# Sheet1.net
KiCad netlist of a schematic drawn in Altium Designer
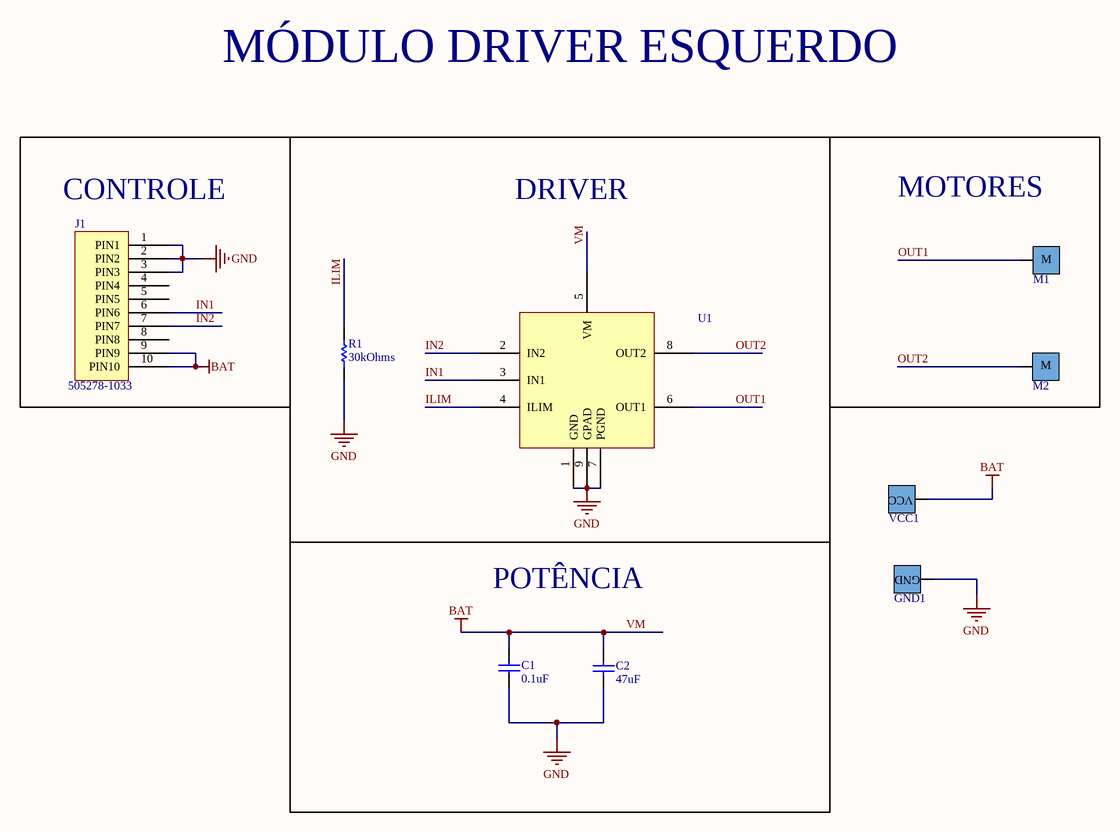
[diagram p0: Sheet1.SchDoc]

(export (version "E")
  (design (tool "Eeschema 10.0.6"))
  (components
    (comp (ref "C1")
      (value "0.1uF")
      (footprint "C0805")
      (description "CAP CER 100nF 25V X7R 0805")
      (fields
        (field (name "MANUFACTURER") "Kemet")
        (field (name "PART NUMBER") "C0805C104M3RACTU")
        (field (name "LIBRARY CONTROL - PERSON THAT CHECKED FOOTPRINT") "Cage")
        (field (name "LIBRARY CONTROL - PERSON THAT CHECKED SCHEMATIC") "Cage")
        (field (name "LIBRARY CONTROL - PERSON THAT DID THE LAST UPDATE FOOTPRINT") "Cage")
        (field (name "LIBRARY CONTROL - PERSON THAT DID THE LAST UPDATE SCHEMATIC") "Cage")
      )
      (libsource (lib "Uai!Tecas") (part "C0805C104M3RACTU"))
    )
    (comp (ref "C2")
      (value "47uF")
      (footprint "C1210")
      (description "CAP CER 47uF 16V X6S 1210")
      (fields
        (field (name "MANUFACTURER") "Murata")
        (field (name "PART NUMBER") "GRM32EC81C476KE15K")
        (field (name "LIBRARY CONTROL - PERSON THAT CHECKED FOOTPRINT") "Cage")
        (field (name "LIBRARY CONTROL - PERSON THAT CHECKED SCHEMATIC") "Cage")
        (field (name "LIBRARY CONTROL - PERSON THAT DID THE LAST UPDATE FOOTPRINT") "Prisma")
        (field (name "LIBRARY CONTROL - PERSON THAT DID THE LAST UPDATE SCHEMATIC") "Prisma")
      )
      (libsource (lib "Capacitor") (part "GRM32EC81C476KE15K"))
    )
    (comp (ref "GND1")
      (value "Ground Pad")
      (footprint "PAD_ALIMENTAÇÃO_MINI")
      (description "GND PAD MINI SUMÔ")
      (libsource (lib "Uai!Tecas") (part "Ground Pad Mini Sumô"))
    )
    (comp (ref "J1")
      (value "505278-1033")
      (footprint "FPC_CON")
      (description "CONN FFC/FPC HORZ 10POS 0.50MM")
      (fields
        (field (name "MANUFACTURER") "Molex")
        (field (name "LIBRARY CONTROL - PERSON THAT CHECKED FOOTPRINT") "Lucas")
        (field (name "LIBRARY CONTROL - PERSON THAT CHECKED SCHEMATIC") "Lucas")
        (field (name "LIBRARY CONTROL - PERSON THAT DID THE LAST UPDATE FOOTPRINT") "Mateus(Dimas)")
        (field (name "LIBRARY CONTROL - PERSON THAT DID THE LAST UPDATE SCHEMATIC") "Mateus(Dimas)")
      )
      (libsource (lib "Uai!Tecas") (part "505278-1033_BODY"))
    )
    (comp (ref "M1")
      (value "Motor Pad")
      (footprint "PAD_MOTOR_MINI")
      (description "MOTOR PAD MINI SUMÔ")
      (libsource (lib "Uai!Tecas") (part "Motor Pad Mini Sumô"))
    )
    (comp (ref "M2")
      (value "Motor Pad")
      (footprint "PAD_MOTOR_MINI")
      (description "MOTOR PAD MINI SUMÔ")
      (libsource (lib "Uai!Tecas") (part "Motor Pad Mini Sumô"))
    )
    (comp (ref "R1")
      (value "30kOhms")
      (footprint "RESC1608X55N")
      (description "RES SMD 30 kOHMS 1% 1/10W 0603")
      (fields
        (field (name "MANUFACTURER") "YAGEO")
        (field (name "PART NUMBER") "RC0603FR-0730KL")
        (field (name "LIBRARY CONTROL - PERSON THAT CHECKED FOOTPRINT") "Guilherme")
        (field (name "LIBRARY CONTROL - PERSON THAT CHECKED SCHEMATIC") "Guilherme")
        (field (name "LIBRARY CONTROL - PERSON THAT DID THE LAST UPDATE FOOTPRINT") "Guilherme")
        (field (name "LIBRARY CONTROL - PERSON THAT DID THE LAST UPDATE SCHEMATIC") "Guilherme")
      )
      (libsource (lib "Uai!Tecas") (part "RC0603FR-0730KL"))
    )
    (comp (ref "U1")
      (value "DRV8871DDA")
      (footprint "SO-PowerPad-8(8_pins)")
      (description "IC MTR DRV (6.5V ~ 45V) (3.5 A) SO-PowerPad-8")
      (fields
        (field (name "MANUFACTURER") "Texas Instruments")
        (field (name "LIBRARY CONTROL - PERSON THAT CHECKED SCHEMATIC") "Stéfany (Ster)")
        (field (name "LIBRARY CONTROL - PERSON THAT CHECKED FOOTPRINT") "Stéfany (Ster)")
        (field (name "LIBRARY CONTROL - PERSON THAT DID THE LAST UPDATE SCHEMATIC") "Stéfany (Ster)")
        (field (name "LIBRARY CONTROL - PERSON THAT DID THE LAST UPDATE FOOTPRINT") "Maria Laura")
      )
      (libsource (lib "Uai!Tecas") (part "DRV8871DDA"))
    )
    (comp (ref "VCC1")
      (value "Source Pad")
      (footprint "PAD_ALIMENTAÇÃO_MINI")
      (description "VCC PAD MINI SUMÔ")
      (libsource (lib "Uai!Tecas") (part "Source Pad Mini Sumô"))
    )
  )
  (nets
    (net (code "1") (name "/ILIM") (class "Default")
      (node (ref "R1") (pin "1") (pinfunction "1_1") (pintype "passive"))
      (node (ref "U1") (pin "4") (pinfunction "ILIM_4") (pintype "passive"))
    )
    (net (code "2") (name "/IN1") (class "Default")
      (node (ref "J1") (pin "6") (pinfunction "PIN6_6") (pintype "passive"))
      (node (ref "U1") (pin "3") (pinfunction "IN1_3") (pintype "passive"))
    )
    (net (code "3") (name "/IN2") (class "Default")
      (node (ref "J1") (pin "7") (pinfunction "PIN7_7") (pintype "passive"))
      (node (ref "U1") (pin "2") (pinfunction "IN2_2") (pintype "passive"))
    )
    (net (code "4") (name "/OUT1") (class "Default")
      (node (ref "M1") (pin "M") (pinfunction "M_M") (pintype "passive"))
      (node (ref "U1") (pin "6") (pinfunction "OUT1_6") (pintype "passive"))
    )
    (net (code "5") (name "/OUT2") (class "Default")
      (node (ref "M2") (pin "M") (pinfunction "M_M") (pintype "passive"))
      (node (ref "U1") (pin "8") (pinfunction "OUT2_8") (pintype "passive"))
    )
    (net (code "6") (name "BAT") (class "Default")
      (node (ref "C1") (pin "2") (pinfunction "2_2") (pintype "passive"))
      (node (ref "C2") (pin "2") (pinfunction "2_2") (pintype "passive"))
      (node (ref "J1") (pin "10") (pinfunction "PIN10_10") (pintype "passive"))
      (node (ref "J1") (pin "9") (pinfunction "PIN9_9") (pintype "passive"))
      (node (ref "U1") (pin "5") (pinfunction "VM_5") (pintype "passive"))
      (node (ref "VCC1") (pin "A") (pinfunction "VCC_A") (pintype "passive"))
    )
    (net (code "7") (name "GND") (class "Default")
      (node (ref "C1") (pin "1") (pinfunction "1_1") (pintype "passive"))
      (node (ref "C2") (pin "1") (pinfunction "1_1") (pintype "passive"))
      (node (ref "GND1") (pin "A") (pinfunction "GND_A") (pintype "passive"))
      (node (ref "J1") (pin "1") (pinfunction "PIN1_1") (pintype "passive"))
      (node (ref "J1") (pin "2") (pinfunction "PIN2_2") (pintype "passive"))
      (node (ref "J1") (pin "3") (pinfunction "PIN3_3") (pintype "passive"))
      (node (ref "R1") (pin "2") (pinfunction "2_2") (pintype "passive"))
      (node (ref "U1") (pin "1") (pinfunction "GND_1") (pintype "passive"))
      (node (ref "U1") (pin "7") (pinfunction "PGND_7") (pintype "passive"))
      (node (ref "U1") (pin "9") (pinfunction "GPAD_9") (pintype "passive"))
    )
    (net (code "8") (name "unconnected-(J1-PIN4-Pad4)") (class "Default")
      (node (ref "J1") (pin "4") (pinfunction "PIN4_4") (pintype "passive"))
    )
    (net (code "9") (name "unconnected-(J1-PIN5-Pad5)") (class "Default")
      (node (ref "J1") (pin "5") (pinfunction "PIN5_5") (pintype "passive"))
    )
    (net (code "10") (name "unconnected-(J1-PIN8-Pad8)") (class "Default")
      (node (ref "J1") (pin "8") (pinfunction "PIN8_8") (pintype "passive"))
    )
  )
)
